# 1-Schematic_CarFan_controller_v2_0.net
KiCad netlist of a schematic drawn in EasyEDA
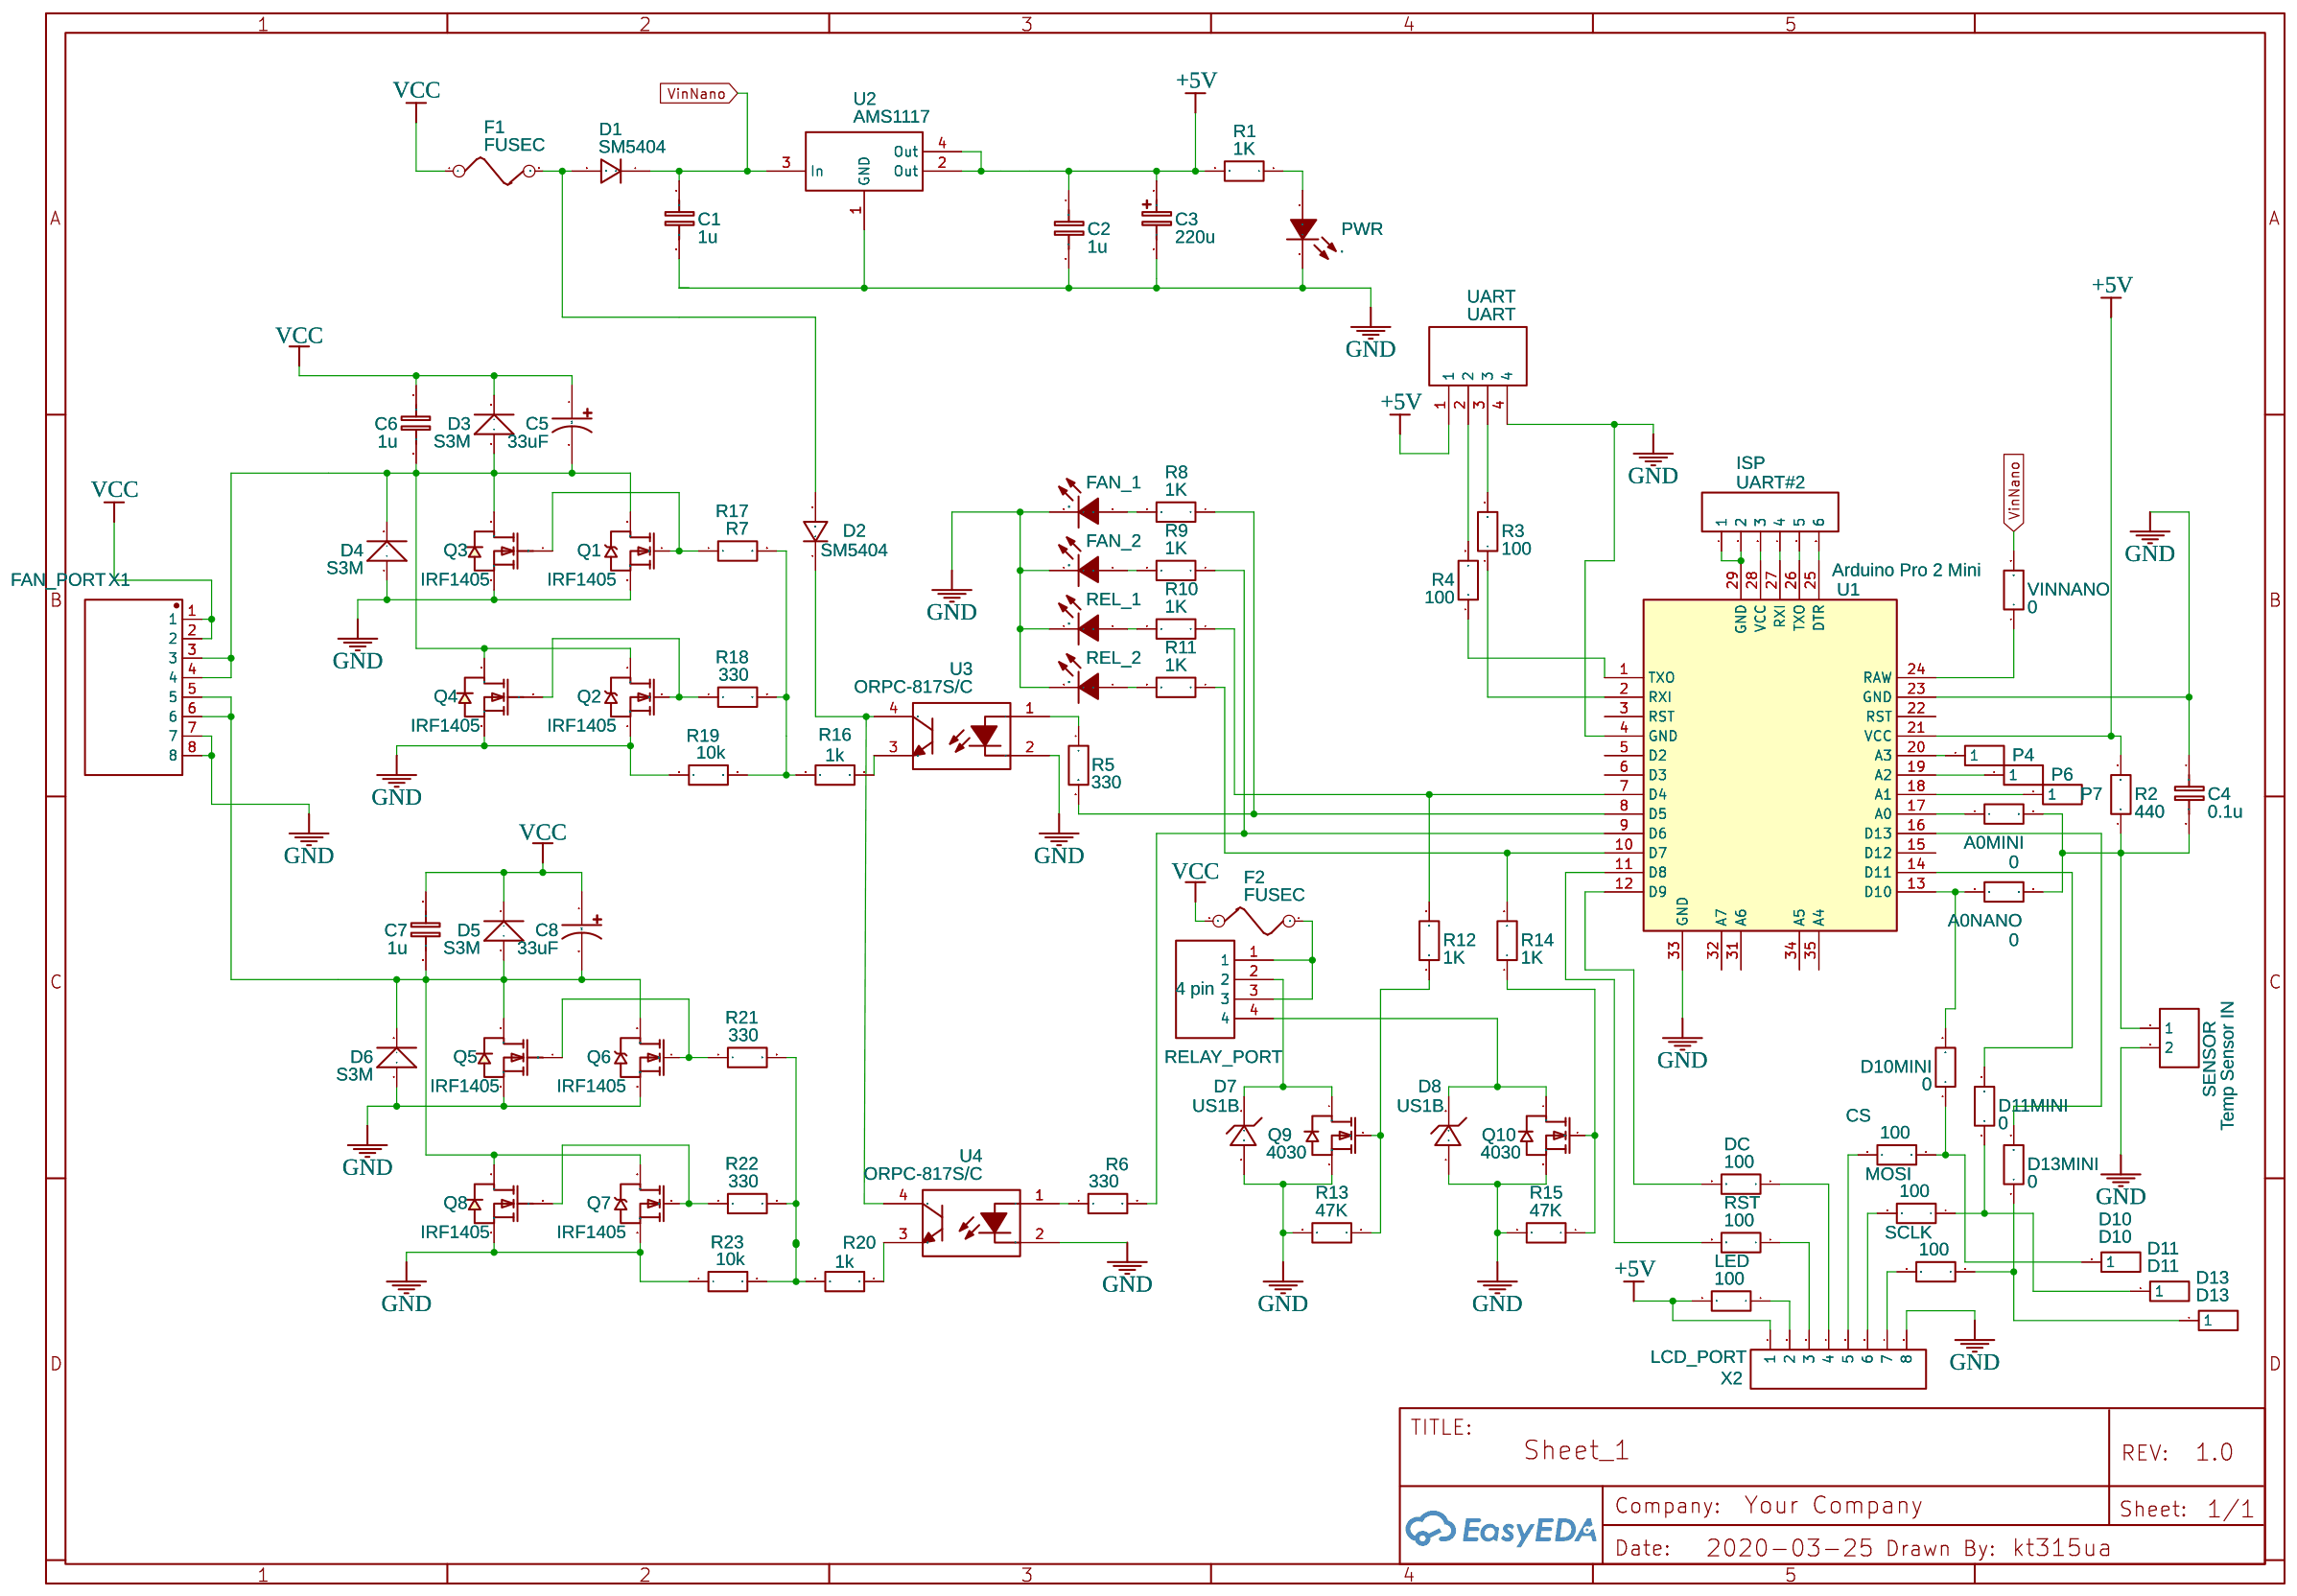
[diagram p0: schematic sheet]

(export (version "E")
  (design (tool "Eeschema 10.0.6"))
  (components
    (comp (ref "A0MINI") (value "0") (libsource (lib "") (part "Res_1206(1/4W)_EU_15")))
    (comp (ref "A0NANO") (value "0") (libsource (lib "") (part "Res_1206(1/4W)_EU_12")))
    (comp (ref "C1") (value "1u") (libsource (lib "") (part "Cap_1206_EU_4")))
    (comp (ref "C2") (value "1u") (libsource (lib "") (part "Cap_1206_EU_2")))
    (comp (ref "C3") (value "220u") (libsource (lib "") (part "Cap_Electrolytic(SMD)_D6.3XH5.5_EU")))
    (comp (ref "C4") (value "0.1u") (libsource (lib "") (part "Cap_1206_EU_3")))
    (comp (ref "C5")
      (value "33uF")
      (fields
        (field (name "BOM_Manufacturer Part") "EEEFK2A330P")
        (field (name "BOM_Supplier Part") "C178571")
      )
      (libsource (lib "") (part "EEEFK2A330P"))
    )
    (comp (ref "C6") (value "1u") (libsource (lib "") (part "Cap_1206_EU_1")))
    (comp (ref "C7") (value "1u") (libsource (lib "") (part "Cap_1206_EU")))
    (comp (ref "C8")
      (value "33uF")
      (fields
        (field (name "BOM_Manufacturer Part") "EEEFK2A330P")
        (field (name "BOM_Supplier Part") "C178571")
      )
      (libsource (lib "") (part "EEEFK2A330P"))
    )
    (comp (ref "CS") (value "100") (libsource (lib "") (part "Res_1206(1/4W)_EU_14")))
    (comp (ref "D1")
      (value "SM5404")
      (fields (field (name "BOM_Supplier Part") "C212808"))
      (libsource (lib "") (part "SM5404"))
    )
    (comp (ref "D2")
      (value "SM5404")
      (fields (field (name "BOM_Supplier Part") "C212808"))
      (libsource (lib "") (part "SM5404_1"))
    )
    (comp (ref "D3") (value "S3M") (libsource (lib "") (part "DDO-214AB")))
    (comp (ref "D4") (value "S3M") (libsource (lib "") (part "DDO-214AB")))
    (comp (ref "D5") (value "S3M") (libsource (lib "") (part "DDO-214AB")))
    (comp (ref "D6") (value "S3M") (libsource (lib "") (part "DDO-214AB")))
    (comp (ref "D7")
      (value "US1B")
      (fields
        (field (name "BOM_Manufacturer Part") "SMAZ12-13-F")
        (field (name "BOM_Supplier Part") "C110523")
      )
      (libsource (lib "") (part "SMAZ12-13-F(SMA(DO-214AC))"))
    )
    (comp (ref "D8")
      (value "US1B")
      (fields
        (field (name "BOM_Manufacturer Part") "SMAZ12-13-F")
        (field (name "BOM_Supplier Part") "C110523")
      )
      (libsource (lib "") (part "SMAZ12-13-F(SMA(DO-214AC))"))
    )
    (comp (ref "D10")
      (value "D10")
      (fields
        (field (name "BOM_Manufacturer Part") "Header-Male-2.54_1x1")
        (field (name "BOM_Supplier Part") "C81276")
      )
      (libsource (lib "") (part "Header-Male-2.54_1x1_1"))
    )
    (comp (ref "D10MINI") (value "0") (libsource (lib "") (part "Res_1206(1/4W)_EU_4")))
    (comp (ref "D11")
      (value "D11")
      (fields
        (field (name "BOM_Manufacturer Part") "Header-Male-2.54_1x1")
        (field (name "BOM_Supplier Part") "C81276")
      )
      (libsource (lib "") (part "Header-Male-2.54_1x1_1"))
    )
    (comp (ref "D11MINI") (value "0") (libsource (lib "") (part "Res_1206(1/4W)_EU_11")))
    (comp (ref "D13")
      (value "D13")
      (fields
        (field (name "BOM_Manufacturer Part") "Header-Male-2.54_1x1")
        (field (name "BOM_Supplier Part") "C81276")
      )
      (libsource (lib "") (part "Header-Male-2.54_1x1_1"))
    )
    (comp (ref "D13MINI") (value "0") (libsource (lib "") (part "Res_1206(1/4W)_EU_2")))
    (comp (ref "DC") (value "100") (libsource (lib "") (part "Res_1206(1/4W)_EU_9")))
    (comp (ref "F1") (value "FUSEC") (libsource (lib "") (part "FUSEC_1")))
    (comp (ref "F2") (value "FUSEC") (libsource (lib "") (part "FUSEC")))
    (comp (ref "FAN_1")
      (value ".")
      (fields
        (field (name "BOM_Manufacturer Part") "KT-1206Red LED")
        (field (name "BOM_Supplier Part") "C49018")
      )
      (libsource (lib "") (part "KT-1206Red LED"))
    )
    (comp (ref "FAN_2")
      (value ".")
      (fields
        (field (name "BOM_Manufacturer Part") "KT-1206Red LED")
        (field (name "BOM_Supplier Part") "C49018")
      )
      (libsource (lib "") (part "KT-1206Red LED"))
    )
    (comp (ref "FAN_PORT")
      (value "X1")
      (fields
        (field (name "BOM_Manufacturer Part") "Connector KF2510-8A")
        (field (name "BOM_Supplier Part") "C27837")
      )
      (libsource (lib "") (part "Connector_KF2510-8A-Fix"))
    )
    (comp (ref "ISP")
      (value "UART#2")
      (fields
        (field (name "BOM_Manufacturer Part") "Female header 1*6p")
        (field (name "BOM_Supplier Part") "C40877")
      )
      (libsource (lib "") (part "Header-Female-2.54_1x6"))
    )
    (comp (ref "LCD_PORT")
      (value "X2")
      (fields
        (field (name "BOM_Manufacturer Part") "Female headerHDR1X8-2.54")
        (field (name "BOM_Supplier Part") "C27438")
      )
      (libsource (lib "") (part "Header-Female-2.54_1x8"))
    )
    (comp (ref "LED") (value "100") (libsource (lib "") (part "Res_1206(1/4W)_EU_10")))
    (comp (ref "MOSI") (value "100") (libsource (lib "") (part "Res_1206(1/4W)_EU_3")))
    (comp (ref "P4")
      (value "D13")
      (fields
        (field (name "BOM_Manufacturer Part") "Header-Male-2.54_1x1")
        (field (name "BOM_Supplier Part") "C81276")
      )
      (libsource (lib "") (part "Header-Male-2.54_1x1"))
    )
    (comp (ref "P6")
      (value "D13")
      (fields
        (field (name "BOM_Manufacturer Part") "Header-Male-2.54_1x1")
        (field (name "BOM_Supplier Part") "C81276")
      )
      (libsource (lib "") (part "Header-Male-2.54_1x1"))
    )
    (comp (ref "P7")
      (value "D13")
      (fields
        (field (name "BOM_Manufacturer Part") "Header-Male-2.54_1x1")
        (field (name "BOM_Supplier Part") "C81276")
      )
      (libsource (lib "") (part "Header-Male-2.54_1x1"))
    )
    (comp (ref "PWR")
      (value ".")
      (fields
        (field (name "BOM_Manufacturer Part") "KT-1206Red LED")
        (field (name "BOM_Supplier Part") "C49018")
      )
      (libsource (lib "") (part "KT-1206Red LED_2"))
    )
    (comp (ref "Q1")
      (value "IRF1405")
      (fields
        (field (name "BOM_Manufacturer Part") "IRF1405ZSTRLPBF")
        (field (name "BOM_Supplier Part") "C459941")
      )
      (libsource (lib "") (part "IRF1405ZSTRLPBF"))
    )
    (comp (ref "Q2")
      (value "IRF1405")
      (fields
        (field (name "BOM_Manufacturer Part") "IRF1405ZSTRLPBF")
        (field (name "BOM_Supplier Part") "C459941")
      )
      (libsource (lib "") (part "IRF1405ZSTRLPBF"))
    )
    (comp (ref "Q3")
      (value "IRF1405")
      (fields (field (name "BOM_Manufacturer Part") "IRF1405PBF") (field (name "BOM_Supplier Part") "C2559"))
      (libsource (lib "") (part "IRF1405PBF"))
    )
    (comp (ref "Q4")
      (value "IRF1405")
      (fields (field (name "BOM_Manufacturer Part") "IRF1405PBF") (field (name "BOM_Supplier Part") "C2559"))
      (libsource (lib "") (part "IRF1405PBF"))
    )
    (comp (ref "Q5")
      (value "IRF1405")
      (fields (field (name "BOM_Manufacturer Part") "IRF1405PBF") (field (name "BOM_Supplier Part") "C2559"))
      (libsource (lib "") (part "IRF1405PBF"))
    )
    (comp (ref "Q6")
      (value "IRF1405")
      (fields
        (field (name "BOM_Manufacturer Part") "IRF1405ZSTRLPBF")
        (field (name "BOM_Supplier Part") "C459941")
      )
      (libsource (lib "") (part "IRF1405ZSTRLPBF"))
    )
    (comp (ref "Q7")
      (value "IRF1405")
      (fields
        (field (name "BOM_Manufacturer Part") "IRF1405ZSTRLPBF")
        (field (name "BOM_Supplier Part") "C459941")
      )
      (libsource (lib "") (part "IRF1405ZSTRLPBF"))
    )
    (comp (ref "Q8")
      (value "IRF1405")
      (fields (field (name "BOM_Manufacturer Part") "IRF1405PBF") (field (name "BOM_Supplier Part") "C2559"))
      (libsource (lib "") (part "IRF1405PBF"))
    )
    (comp (ref "Q9")
      (value "4030")
      (fields
        (field (name "BOM_Manufacturer Part") "STD8N60DM2")
        (field (name "BOM_Supplier Part") "C457504")
      )
      (libsource (lib "") (part "STD8N60DM2"))
    )
    (comp (ref "Q10")
      (value "4030")
      (fields
        (field (name "BOM_Manufacturer Part") "STD8N60DM2")
        (field (name "BOM_Supplier Part") "C457504")
      )
      (libsource (lib "") (part "STD8N60DM2"))
    )
    (comp (ref "R1") (value "1K") (libsource (lib "") (part "Res_1206(1/4W)_EU_1")))
    (comp (ref "R2") (value "440") (libsource (lib "") (part "Res_1206(1/4W)_EU_5")))
    (comp (ref "R3") (value "100") (libsource (lib "") (part "Res_1206(1/4W)_EU_5")))
    (comp (ref "R4") (value "100") (libsource (lib "") (part "Res_1206(1/4W)_EU_5")))
    (comp (ref "R5") (value "330") (libsource (lib "") (part "Res_1206(1/4W)_EU_6")))
    (comp (ref "R6") (value "330") (libsource (lib "") (part "Res_1206(1/4W)_EU")))
    (comp (ref "R8") (value "1K") (libsource (lib "") (part "Res_1206(1/4W)_EU_1")))
    (comp (ref "R9") (value "1K") (libsource (lib "") (part "Res_1206(1/4W)_EU_1")))
    (comp (ref "R10") (value "1K") (libsource (lib "") (part "Res_1206(1/4W)_EU_1")))
    (comp (ref "R11") (value "1K") (libsource (lib "") (part "Res_1206(1/4W)_EU_1")))
    (comp (ref "R12") (value "1K") (libsource (lib "") (part "Res_1206(1/4W)_EU_5")))
    (comp (ref "R13") (value "47K") (libsource (lib "") (part "Res_1206(1/4W)_EU_1")))
    (comp (ref "R14") (value "1K") (libsource (lib "") (part "Res_1206(1/4W)_EU_5")))
    (comp (ref "R15") (value "47K") (libsource (lib "") (part "Res_1206(1/4W)_EU_1")))
    (comp (ref "R16") (value "1k") (libsource (lib "") (part "Res_1206(1/4W)_EU_1")))
    (comp (ref "R17") (value "R7") (libsource (lib "") (part "Res_1206(1/4W)_EU")))
    (comp (ref "R18") (value "330") (libsource (lib "") (part "Res_1206(1/4W)_EU")))
    (comp (ref "R19") (value "10k") (libsource (lib "") (part "Res_1206(1/4W)_EU")))
    (comp (ref "R20") (value "1k") (libsource (lib "") (part "Res_1206(1/4W)_EU_1")))
    (comp (ref "R21") (value "330") (libsource (lib "") (part "Res_1206(1/4W)_EU")))
    (comp (ref "R22") (value "330") (libsource (lib "") (part "Res_1206(1/4W)_EU")))
    (comp (ref "R23") (value "10k") (libsource (lib "") (part "Res_1206(1/4W)_EU")))
    (comp (ref "RELAY_PORT")
      (value "4 pin")
      (fields
        (field (name "BOM_Manufacturer Part") "220S-1*4P H=8.5MM Ytype Gold-plated")
        (field (name "BOM_Supplier Part") "C124413")
      )
      (libsource (lib "") (part "220S-1*4P H=8.5MM Ytype Gold-plated"))
    )
    (comp (ref "REL_1")
      (value ".")
      (fields
        (field (name "BOM_Manufacturer Part") "KT-1206Red LED")
        (field (name "BOM_Supplier Part") "C49018")
      )
      (libsource (lib "") (part "KT-1206Red LED_1"))
    )
    (comp (ref "REL_2")
      (value ".")
      (fields
        (field (name "BOM_Manufacturer Part") "KT-1206Red LED")
        (field (name "BOM_Supplier Part") "C49018")
      )
      (libsource (lib "") (part "KT-1206Red LED_1"))
    )
    (comp (ref "RST") (value "100") (libsource (lib "") (part "Res_1206(1/4W)_EU_7")))
    (comp (ref "SCLK") (value "100") (libsource (lib "") (part "Res_1206(1/4W)_EU_8")))
    (comp (ref "SENSOR")
      (value "Temp Sensor IN")
      (fields
        (field (name "BOM_Manufacturer Part") "2.54-1*2PFemale")
        (field (name "BOM_Supplier Part") "C49661")
      )
      (libsource (lib "") (part "Header-Female-2.54_1x2"))
    )
    (comp (ref "U1") (value "Arduino Pro 2 Mini") (libsource (lib "") (part "Arduino Pro 2 Mini_328_-_3.3V")))
    (comp (ref "U2")
      (value "AMS1117")
      (fields (field (name "BOM_Supplier Part") "C6186"))
      (libsource (lib "") (part "AMS1117"))
    )
    (comp (ref "U3")
      (value "ORPC-817S/C")
      (fields (field (name "BOM_Supplier Part") "C231230"))
      (libsource (lib "") (part "ORPC-817S/C"))
    )
    (comp (ref "U4")
      (value "ORPC-817S/C")
      (fields (field (name "BOM_Supplier Part") "C231230"))
      (libsource (lib "") (part "ORPC-817S/C"))
    )
    (comp (ref "UART")
      (value "UART")
      (fields
        (field (name "BOM_Manufacturer Part") "220S-1*4P H=8.5MM Ytype Gold-plated")
        (field (name "BOM_Supplier Part") "C124413")
      )
      (libsource (lib "") (part "220S-1*4P H=8.5MM Ytype Gold-plated_1"))
    )
    (comp (ref "VINNANO") (value "0") (libsource (lib "") (part "Res_1206(1/4W)_EU_13")))
  )
  (nets
    (net (code "1") (name "+5V") (class "Default")
      (node (ref "C2") (pin "1") (pinfunction "1_1") (pintype "unspecified"))
      (node (ref "C3") (pin "1") (pinfunction "1_1") (pintype "unspecified"))
      (node (ref "LCD_PORT") (pin "1") (pinfunction "1_1") (pintype "input"))
      (node (ref "LED") (pin "2") (pinfunction "2_2") (pintype "unspecified"))
      (node (ref "R1") (pin "2") (pinfunction "2_2") (pintype "unspecified"))
      (node (ref "R2") (pin "2") (pinfunction "2_2") (pintype "unspecified"))
      (node (ref "U1") (pin "21") (pinfunction "VCC_21") (pintype "unspecified"))
      (node (ref "U2") (pin "2") (pinfunction "Out_2") (pintype "unspecified"))
      (node (ref "U2") (pin "4") (pinfunction "Out_4") (pintype "unspecified"))
      (node (ref "UART") (pin "1") (pinfunction "1_1") (pintype "unspecified"))
    )
    (net (code "2") (name "GND") (class "Default")
      (node (ref "C1") (pin "2") (pinfunction "2_2") (pintype "unspecified"))
      (node (ref "C2") (pin "2") (pinfunction "2_2") (pintype "unspecified"))
      (node (ref "C3") (pin "2") (pinfunction "2_2") (pintype "unspecified"))
      (node (ref "C4") (pin "1") (pinfunction "1_1") (pintype "unspecified"))
      (node (ref "D4") (pin "1") (pinfunction "+_1") (pintype "unspecified"))
      (node (ref "D6") (pin "1") (pinfunction "+_1") (pintype "unspecified"))
      (node (ref "D7") (pin "1") (pinfunction "A_1") (pintype "unspecified"))
      (node (ref "D8") (pin "1") (pinfunction "A_1") (pintype "unspecified"))
      (node (ref "FAN_1") (pin "2") (pinfunction "K_2") (pintype "unspecified"))
      (node (ref "FAN_2") (pin "2") (pinfunction "K_2") (pintype "unspecified"))
      (node (ref "FAN_PORT") (pin "7") (pinfunction "7_7") (pintype "unspecified"))
      (node (ref "FAN_PORT") (pin "8") (pinfunction "8_8") (pintype "unspecified"))
      (node (ref "LCD_PORT") (pin "8") (pinfunction "8_8") (pintype "input"))
      (node (ref "PWR") (pin "2") (pinfunction "K_2") (pintype "unspecified"))
      (node (ref "Q1") (pin "3") (pinfunction "S_3") (pintype "unspecified"))
      (node (ref "Q10") (pin "3") (pinfunction "S_3") (pintype "unspecified"))
      (node (ref "Q2") (pin "3") (pinfunction "S_3") (pintype "unspecified"))
      (node (ref "Q3") (pin "3") (pinfunction "S_3") (pintype "unspecified"))
      (node (ref "Q4") (pin "3") (pinfunction "S_3") (pintype "unspecified"))
      (node (ref "Q5") (pin "3") (pinfunction "S_3") (pintype "unspecified"))
      (node (ref "Q6") (pin "3") (pinfunction "S_3") (pintype "unspecified"))
      (node (ref "Q7") (pin "3") (pinfunction "S_3") (pintype "unspecified"))
      (node (ref "Q8") (pin "3") (pinfunction "S_3") (pintype "unspecified"))
      (node (ref "Q9") (pin "3") (pinfunction "S_3") (pintype "unspecified"))
      (node (ref "R13") (pin "2") (pinfunction "2_2") (pintype "unspecified"))
      (node (ref "R15") (pin "2") (pinfunction "2_2") (pintype "unspecified"))
      (node (ref "R19") (pin "1") (pinfunction "1_1") (pintype "unspecified"))
      (node (ref "R23") (pin "1") (pinfunction "1_1") (pintype "unspecified"))
      (node (ref "REL_1") (pin "2") (pinfunction "K_2") (pintype "unspecified"))
      (node (ref "REL_2") (pin "2") (pinfunction "K_2") (pintype "unspecified"))
      (node (ref "SENSOR") (pin "2") (pinfunction "2_2") (pintype "input"))
      (node (ref "U1") (pin "23") (pinfunction "GND_23") (pintype "unspecified"))
      (node (ref "U1") (pin "33") (pinfunction "GND_33") (pintype "unspecified"))
      (node (ref "U1") (pin "4") (pinfunction "GND_4") (pintype "unspecified"))
      (node (ref "U2") (pin "1") (pinfunction "GND_1") (pintype "unspecified"))
      (node (ref "U3") (pin "2") (pinfunction "2_2") (pintype "unspecified"))
      (node (ref "U4") (pin "2") (pinfunction "2_2") (pintype "unspecified"))
      (node (ref "UART") (pin "4") (pinfunction "4_4") (pintype "unspecified"))
    )
    (net (code "3") (name "Net-(A0MINI-Pad2)") (class "Default")
      (node (ref "A0MINI") (pin "2") (pinfunction "2_2") (pintype "unspecified"))
      (node (ref "A0NANO") (pin "2") (pinfunction "2_2") (pintype "unspecified"))
      (node (ref "C4") (pin "2") (pinfunction "2_2") (pintype "unspecified"))
      (node (ref "R2") (pin "1") (pinfunction "1_1") (pintype "unspecified"))
      (node (ref "SENSOR") (pin "1") (pinfunction "1_1") (pintype "input"))
    )
    (net (code "4") (name "Net-(CS-Pad1)") (class "Default")
      (node (ref "CS") (pin "1") (pinfunction "1_1") (pintype "unspecified"))
      (node (ref "D10") (pin "1") (pinfunction "1_1") (pintype "input"))
      (node (ref "D10MINI") (pin "1") (pinfunction "1_1") (pintype "unspecified"))
    )
    (net (code "5") (name "Net-(CS-Pad2)") (class "Default")
      (node (ref "CS") (pin "2") (pinfunction "2_2") (pintype "unspecified"))
      (node (ref "LCD_PORT") (pin "5") (pinfunction "5_5") (pintype "input"))
    )
    (net (code "6") (name "Net-(D1-Pad2)") (class "Default")
      (node (ref "D1") (pin "2") (pinfunction "2_2") (pintype "unspecified"))
      (node (ref "D2") (pin "2") (pinfunction "2_2") (pintype "unspecified"))
      (node (ref "F1") (pin "2") (pinfunction "2_2") (pintype "unspecified"))
    )
    (net (code "7") (name "Net-(D2-Pad1)") (class "Default")
      (node (ref "D2") (pin "1") (pinfunction "1_1") (pintype "unspecified"))
      (node (ref "U3") (pin "4") (pinfunction "4_4") (pintype "unspecified"))
      (node (ref "U4") (pin "4") (pinfunction "4_4") (pintype "unspecified"))
    )
    (net (code "8") (name "Net-(D3-+)") (class "Default")
      (node (ref "C5") (pin "2") (pinfunction "2_2") (pintype "unspecified"))
      (node (ref "C6") (pin "2") (pinfunction "2_2") (pintype "unspecified"))
      (node (ref "D3") (pin "1") (pinfunction "+_1") (pintype "unspecified"))
      (node (ref "D4") (pin "2") (pinfunction "-_2") (pintype "unspecified"))
      (node (ref "FAN_PORT") (pin "3") (pinfunction "3_3") (pintype "unspecified"))
      (node (ref "FAN_PORT") (pin "4") (pinfunction "4_4") (pintype "unspecified"))
      (node (ref "Q1") (pin "2") (pinfunction "D_2") (pintype "unspecified"))
      (node (ref "Q2") (pin "2") (pinfunction "D_2") (pintype "unspecified"))
      (node (ref "Q3") (pin "2") (pinfunction "D_2") (pintype "unspecified"))
      (node (ref "Q4") (pin "2") (pinfunction "D_2") (pintype "unspecified"))
    )
    (net (code "9") (name "Net-(D5-+)") (class "Default")
      (node (ref "C7") (pin "2") (pinfunction "2_2") (pintype "unspecified"))
      (node (ref "C8") (pin "2") (pinfunction "2_2") (pintype "unspecified"))
      (node (ref "D5") (pin "1") (pinfunction "+_1") (pintype "unspecified"))
      (node (ref "D6") (pin "2") (pinfunction "-_2") (pintype "unspecified"))
      (node (ref "FAN_PORT") (pin "5") (pinfunction "5_5") (pintype "unspecified"))
      (node (ref "FAN_PORT") (pin "6") (pinfunction "6_6") (pintype "unspecified"))
      (node (ref "Q5") (pin "2") (pinfunction "D_2") (pintype "unspecified"))
      (node (ref "Q6") (pin "2") (pinfunction "D_2") (pintype "unspecified"))
      (node (ref "Q7") (pin "2") (pinfunction "D_2") (pintype "unspecified"))
      (node (ref "Q8") (pin "2") (pinfunction "D_2") (pintype "unspecified"))
    )
    (net (code "10") (name "Net-(D7-K)") (class "Default")
      (node (ref "D7") (pin "2") (pinfunction "K_2") (pintype "unspecified"))
      (node (ref "Q9") (pin "4") (pinfunction "D_4") (pintype "unspecified"))
      (node (ref "RELAY_PORT") (pin "2") (pinfunction "2_2") (pintype "unspecified"))
    )
    (net (code "11") (name "Net-(D8-K)") (class "Default")
      (node (ref "D8") (pin "2") (pinfunction "K_2") (pintype "unspecified"))
      (node (ref "Q10") (pin "4") (pinfunction "D_4") (pintype "unspecified"))
      (node (ref "RELAY_PORT") (pin "4") (pinfunction "4_4") (pintype "unspecified"))
    )
    (net (code "12") (name "Net-(D11-Pad1)") (class "Default")
      (node (ref "D11") (pin "1") (pinfunction "1_1") (pintype "input"))
      (node (ref "D11MINI") (pin "1") (pinfunction "1_1") (pintype "unspecified"))
      (node (ref "MOSI") (pin "1") (pinfunction "1_1") (pintype "unspecified"))
    )
    (net (code "13") (name "Net-(D13-Pad1)") (class "Default")
      (node (ref "D13") (pin "1") (pinfunction "1_1") (pintype "input"))
      (node (ref "D13MINI") (pin "1") (pinfunction "1_1") (pintype "unspecified"))
      (node (ref "SCLK") (pin "1") (pinfunction "1_1") (pintype "unspecified"))
    )
    (net (code "14") (name "Net-(DC-Pad1)") (class "Default")
      (node (ref "DC") (pin "1") (pinfunction "1_1") (pintype "unspecified"))
      (node (ref "LCD_PORT") (pin "4") (pinfunction "4_4") (pintype "input"))
    )
    (net (code "15") (name "Net-(F2-Pad1)") (class "Default")
      (node (ref "F2") (pin "1") (pinfunction "1_1") (pintype "unspecified"))
      (node (ref "RELAY_PORT") (pin "1") (pinfunction "1_1") (pintype "unspecified"))
      (node (ref "RELAY_PORT") (pin "3") (pinfunction "3_3") (pintype "unspecified"))
    )
    (net (code "16") (name "Net-(FAN_1-A)") (class "Default")
      (node (ref "FAN_1") (pin "1") (pinfunction "A_1") (pintype "unspecified"))
      (node (ref "R8") (pin "2") (pinfunction "2_2") (pintype "unspecified"))
    )
    (net (code "17") (name "Net-(FAN_2-A)") (class "Default")
      (node (ref "FAN_2") (pin "1") (pinfunction "A_1") (pintype "unspecified"))
      (node (ref "R9") (pin "2") (pinfunction "2_2") (pintype "unspecified"))
    )
    (net (code "18") (name "Net-(ISP-Pad1)") (class "Default")
      (node (ref "ISP") (pin "1") (pinfunction "1_1") (pintype "input"))
      (node (ref "ISP") (pin "2") (pinfunction "2_2") (pintype "input"))
      (node (ref "U1") (pin "29") (pinfunction "GND_29") (pintype "unspecified"))
    )
    (net (code "19") (name "Net-(ISP-Pad3)") (class "Default")
      (node (ref "ISP") (pin "3") (pinfunction "3_3") (pintype "input"))
      (node (ref "U1") (pin "28") (pinfunction "VCC_28") (pintype "unspecified"))
    )
    (net (code "20") (name "Net-(ISP-Pad4)") (class "Default")
      (node (ref "ISP") (pin "4") (pinfunction "4_4") (pintype "input"))
      (node (ref "U1") (pin "27") (pinfunction "RXI_27") (pintype "unspecified"))
    )
    (net (code "21") (name "Net-(ISP-Pad5)") (class "Default")
      (node (ref "ISP") (pin "5") (pinfunction "5_5") (pintype "input"))
      (node (ref "U1") (pin "26") (pinfunction "TXO_26") (pintype "unspecified"))
    )
    (net (code "22") (name "Net-(LCD_PORT-Pad2)") (class "Default")
      (node (ref "LCD_PORT") (pin "2") (pinfunction "2_2") (pintype "input"))
      (node (ref "LED") (pin "1") (pinfunction "1_1") (pintype "unspecified"))
    )
    (net (code "23") (name "Net-(LCD_PORT-Pad3)") (class "Default")
      (node (ref "LCD_PORT") (pin "3") (pinfunction "3_3") (pintype "input"))
      (node (ref "RST") (pin "1") (pinfunction "1_1") (pintype "unspecified"))
    )
    (net (code "24") (name "Net-(LCD_PORT-Pad6)") (class "Default")
      (node (ref "LCD_PORT") (pin "6") (pinfunction "6_6") (pintype "input"))
      (node (ref "MOSI") (pin "2") (pinfunction "2_2") (pintype "unspecified"))
    )
    (net (code "25") (name "Net-(LCD_PORT-Pad7)") (class "Default")
      (node (ref "LCD_PORT") (pin "7") (pinfunction "7_7") (pintype "input"))
      (node (ref "SCLK") (pin "2") (pinfunction "2_2") (pintype "unspecified"))
    )
    (net (code "26") (name "Net-(PWR-A)") (class "Default")
      (node (ref "PWR") (pin "1") (pinfunction "A_1") (pintype "unspecified"))
      (node (ref "R1") (pin "1") (pinfunction "1_1") (pintype "unspecified"))
    )
    (net (code "27") (name "Net-(Q1-G)") (class "Default")
      (node (ref "Q1") (pin "1") (pinfunction "G_1") (pintype "unspecified"))
      (node (ref "Q3") (pin "1") (pinfunction "G_1") (pintype "unspecified"))
      (node (ref "R17") (pin "1") (pinfunction "1_1") (pintype "unspecified"))
    )
    (net (code "28") (name "Net-(Q2-G)") (class "Default")
      (node (ref "Q2") (pin "1") (pinfunction "G_1") (pintype "unspecified"))
      (node (ref "Q4") (pin "1") (pinfunction "G_1") (pintype "unspecified"))
      (node (ref "R18") (pin "1") (pinfunction "1_1") (pintype "unspecified"))
    )
    (net (code "29") (name "Net-(Q5-G)") (class "Default")
      (node (ref "Q5") (pin "1") (pinfunction "G_1") (pintype "unspecified"))
      (node (ref "Q6") (pin "1") (pinfunction "G_1") (pintype "unspecified"))
      (node (ref "R21") (pin "1") (pinfunction "1_1") (pintype "unspecified"))
    )
    (net (code "30") (name "Net-(Q7-G)") (class "Default")
      (node (ref "Q7") (pin "1") (pinfunction "G_1") (pintype "unspecified"))
      (node (ref "Q8") (pin "1") (pinfunction "G_1") (pintype "unspecified"))
      (node (ref "R22") (pin "1") (pinfunction "1_1") (pintype "unspecified"))
    )
    (net (code "31") (name "Net-(Q9-G)") (class "Default")
      (node (ref "Q9") (pin "1") (pinfunction "G_1") (pintype "unspecified"))
      (node (ref "R12") (pin "1") (pinfunction "1_1") (pintype "unspecified"))
      (node (ref "R13") (pin "1") (pinfunction "1_1") (pintype "unspecified"))
    )
    (net (code "32") (name "Net-(Q10-G)") (class "Default")
      (node (ref "Q10") (pin "1") (pinfunction "G_1") (pintype "unspecified"))
      (node (ref "R14") (pin "1") (pinfunction "1_1") (pintype "unspecified"))
      (node (ref "R15") (pin "1") (pinfunction "1_1") (pintype "unspecified"))
    )
    (net (code "33") (name "Net-(R3-Pad1)") (class "Default")
      (node (ref "R3") (pin "1") (pinfunction "1_1") (pintype "unspecified"))
      (node (ref "U1") (pin "2") (pinfunction "RXI_2") (pintype "unspecified"))
    )
    (net (code "34") (name "Net-(R3-Pad2)") (class "Default")
      (node (ref "R3") (pin "2") (pinfunction "2_2") (pintype "unspecified"))
      (node (ref "UART") (pin "3") (pinfunction "3_3") (pintype "unspecified"))
    )
    (net (code "35") (name "Net-(R4-Pad1)") (class "Default")
      (node (ref "R4") (pin "1") (pinfunction "1_1") (pintype "unspecified"))
      (node (ref "U1") (pin "1") (pinfunction "TXO_1") (pintype "unspecified"))
    )
    (net (code "36") (name "Net-(R4-Pad2)") (class "Default")
      (node (ref "R4") (pin "2") (pinfunction "2_2") (pintype "unspecified"))
      (node (ref "UART") (pin "2") (pinfunction "2_2") (pintype "unspecified"))
    )
    (net (code "37") (name "Net-(R5-Pad1)") (class "Default")
      (node (ref "R5") (pin "1") (pinfunction "1_1") (pintype "unspecified"))
      (node (ref "U3") (pin "1") (pinfunction "1_1") (pintype "unspecified"))
    )
    (net (code "38") (name "Net-(R6-Pad1)") (class "Default")
      (node (ref "R6") (pin "1") (pinfunction "1_1") (pintype "unspecified"))
      (node (ref "U4") (pin "1") (pinfunction "1_1") (pintype "unspecified"))
    )
    (net (code "39") (name "Net-(R16-Pad1)") (class "Default")
      (node (ref "R16") (pin "1") (pinfunction "1_1") (pintype "unspecified"))
      (node (ref "U3") (pin "3") (pinfunction "3_3") (pintype "unspecified"))
    )
    (net (code "40") (name "Net-(R16-Pad2)") (class "Default")
      (node (ref "R16") (pin "2") (pinfunction "2_2") (pintype "unspecified"))
      (node (ref "R17") (pin "2") (pinfunction "2_2") (pintype "unspecified"))
      (node (ref "R18") (pin "2") (pinfunction "2_2") (pintype "unspecified"))
      (node (ref "R19") (pin "2") (pinfunction "2_2") (pintype "unspecified"))
    )
    (net (code "41") (name "Net-(R20-Pad1)") (class "Default")
      (node (ref "R20") (pin "1") (pinfunction "1_1") (pintype "unspecified"))
      (node (ref "U4") (pin "3") (pinfunction "3_3") (pintype "unspecified"))
    )
    (net (code "42") (name "Net-(R20-Pad2)") (class "Default")
      (node (ref "R20") (pin "2") (pinfunction "2_2") (pintype "unspecified"))
      (node (ref "R21") (pin "2") (pinfunction "2_2") (pintype "unspecified"))
      (node (ref "R22") (pin "2") (pinfunction "2_2") (pintype "unspecified"))
      (node (ref "R23") (pin "2") (pinfunction "2_2") (pintype "unspecified"))
    )
    (net (code "43") (name "Net-(REL_1-A)") (class "Default")
      (node (ref "R10") (pin "2") (pinfunction "2_2") (pintype "unspecified"))
      (node (ref "REL_1") (pin "1") (pinfunction "A_1") (pintype "unspecified"))
    )
    (net (code "44") (name "Net-(REL_2-A)") (class "Default")
      (node (ref "R11") (pin "2") (pinfunction "2_2") (pintype "unspecified"))
      (node (ref "REL_2") (pin "1") (pinfunction "A_1") (pintype "unspecified"))
    )
    (net (code "45") (name "Net-(U1-A0)") (class "Default")
      (node (ref "A0MINI") (pin "1") (pinfunction "1_1") (pintype "unspecified"))
      (node (ref "U1") (pin "17") (pinfunction "A0_17") (pintype "unspecified"))
    )
    (net (code "46") (name "Net-(U1-A1)") (class "Default")
      (node (ref "P7") (pin "1") (pinfunction "1_1") (pintype "input"))
      (node (ref "U1") (pin "18") (pinfunction "A1_18") (pintype "unspecified"))
    )
    (net (code "47") (name "Net-(U1-A2)") (class "Default")
      (node (ref "P6") (pin "1") (pinfunction "1_1") (pintype "input"))
      (node (ref "U1") (pin "19") (pinfunction "A2_19") (pintype "unspecified"))
    )
    (net (code "48") (name "Net-(U1-A3)") (class "Default")
      (node (ref "P4") (pin "1") (pinfunction "1_1") (pintype "input"))
      (node (ref "U1") (pin "20") (pinfunction "A3_20") (pintype "unspecified"))
    )
    (net (code "49") (name "Net-(U1-D4)") (class "Default")
      (node (ref "R10") (pin "1") (pinfunction "1_1") (pintype "unspecified"))
      (node (ref "R12") (pin "2") (pinfunction "2_2") (pintype "unspecified"))
      (node (ref "U1") (pin "7") (pinfunction "D4_7") (pintype "unspecified"))
    )
    (net (code "50") (name "Net-(U1-D5)") (class "Default")
      (node (ref "R5") (pin "2") (pinfunction "2_2") (pintype "unspecified"))
      (node (ref "R8") (pin "1") (pinfunction "1_1") (pintype "unspecified"))
      (node (ref "U1") (pin "8") (pinfunction "D5_8") (pintype "unspecified"))
    )
    (net (code "51") (name "Net-(U1-D6)") (class "Default")
      (node (ref "R6") (pin "2") (pinfunction "2_2") (pintype "unspecified"))
      (node (ref "R9") (pin "1") (pinfunction "1_1") (pintype "unspecified"))
      (node (ref "U1") (pin "9") (pinfunction "D6_9") (pintype "unspecified"))
    )
    (net (code "52") (name "Net-(U1-D7)") (class "Default")
      (node (ref "R11") (pin "1") (pinfunction "1_1") (pintype "unspecified"))
      (node (ref "R14") (pin "2") (pinfunction "2_2") (pintype "unspecified"))
      (node (ref "U1") (pin "10") (pinfunction "D7_10") (pintype "unspecified"))
    )
    (net (code "53") (name "Net-(U1-D8)") (class "Default")
      (node (ref "RST") (pin "2") (pinfunction "2_2") (pintype "unspecified"))
      (node (ref "U1") (pin "11") (pinfunction "D8_11") (pintype "unspecified"))
    )
    (net (code "54") (name "Net-(U1-D9)") (class "Default")
      (node (ref "DC") (pin "2") (pinfunction "2_2") (pintype "unspecified"))
      (node (ref "U1") (pin "12") (pinfunction "D9_12") (pintype "unspecified"))
    )
    (net (code "55") (name "Net-(U1-D10)") (class "Default")
      (node (ref "A0NANO") (pin "1") (pinfunction "1_1") (pintype "unspecified"))
      (node (ref "D10MINI") (pin "2") (pinfunction "2_2") (pintype "unspecified"))
      (node (ref "U1") (pin "13") (pinfunction "D10_13") (pintype "unspecified"))
    )
    (net (code "56") (name "Net-(U1-D11)") (class "Default")
      (node (ref "D11MINI") (pin "2") (pinfunction "2_2") (pintype "unspecified"))
      (node (ref "U1") (pin "14") (pinfunction "D11_14") (pintype "unspecified"))
    )
    (net (code "57") (name "Net-(U1-D13)") (class "Default")
      (node (ref "D13MINI") (pin "2") (pinfunction "2_2") (pintype "unspecified"))
      (node (ref "U1") (pin "16") (pinfunction "D13_16") (pintype "unspecified"))
    )
    (net (code "58") (name "Net-(U1-DTR)") (class "Default")
      (node (ref "ISP") (pin "6") (pinfunction "6_6") (pintype "input"))
      (node (ref "U1") (pin "25") (pinfunction "DTR_25") (pintype "unspecified"))
    )
    (net (code "59") (name "Net-(U1-RAW)") (class "Default")
      (node (ref "U1") (pin "24") (pinfunction "RAW_24") (pintype "unspecified"))
      (node (ref "VINNANO") (pin "1") (pinfunction "1_1") (pintype "unspecified"))
    )
    (net (code "60") (name "VCC") (class "Default")
      (node (ref "C5") (pin "1") (pinfunction "1_1") (pintype "unspecified"))
      (node (ref "C6") (pin "1") (pinfunction "1_1") (pintype "unspecified"))
      (node (ref "C7") (pin "1") (pinfunction "1_1") (pintype "unspecified"))
      (node (ref "C8") (pin "1") (pinfunction "1_1") (pintype "unspecified"))
      (node (ref "D3") (pin "2") (pinfunction "-_2") (pintype "unspecified"))
      (node (ref "D5") (pin "2") (pinfunction "-_2") (pintype "unspecified"))
      (node (ref "F1") (pin "1") (pinfunction "1_1") (pintype "unspecified"))
      (node (ref "F2") (pin "2") (pinfunction "2_2") (pintype "unspecified"))
      (node (ref "FAN_PORT") (pin "1") (pinfunction "1_1") (pintype "unspecified"))
      (node (ref "FAN_PORT") (pin "2") (pinfunction "2_2") (pintype "unspecified"))
    )
    (net (code "61") (name "VinNano") (class "Default")
      (node (ref "C1") (pin "1") (pinfunction "1_1") (pintype "unspecified"))
      (node (ref "D1") (pin "1") (pinfunction "1_1") (pintype "unspecified"))
      (node (ref "U2") (pin "3") (pinfunction "In_3") (pintype "unspecified"))
      (node (ref "VINNANO") (pin "2") (pinfunction "2_2") (pintype "unspecified"))
    )
    (net (code "62") (name "unconnected-(U1-A4-Pad35)") (class "Default")
      (node (ref "U1") (pin "35") (pinfunction "A4_35") (pintype "unspecified"))
    )
    (net (code "63") (name "unconnected-(U1-A5-Pad34)") (class "Default")
      (node (ref "U1") (pin "34") (pinfunction "A5_34") (pintype "unspecified"))
    )
    (net (code "64") (name "unconnected-(U1-A6-Pad31)") (class "Default")
      (node (ref "U1") (pin "31") (pinfunction "A6_31") (pintype "unspecified"))
    )
    (net (code "65") (name "unconnected-(U1-A7-Pad32)") (class "Default")
      (node (ref "U1") (pin "32") (pinfunction "A7_32") (pintype "unspecified"))
    )
    (net (code "66") (name "unconnected-(U1-D2-Pad5)") (class "Default")
      (node (ref "U1") (pin "5") (pinfunction "D2_5") (pintype "unspecified"))
    )
    (net (code "67") (name "unconnected-(U1-D3-Pad6)") (class "Default")
      (node (ref "U1") (pin "6") (pinfunction "D3_6") (pintype "unspecified"))
    )
    (net (code "68") (name "unconnected-(U1-D12-Pad15)") (class "Default")
      (node (ref "U1") (pin "15") (pinfunction "D12_15") (pintype "unspecified"))
    )
    (net (code "69") (name "unconnected-(U1-RST-Pad3)") (class "Default")
      (node (ref "U1") (pin "3") (pinfunction "RST_3") (pintype "unspecified"))
    )
    (net (code "70") (name "unconnected-(U1-RST-Pad22)") (class "Default")
      (node (ref "U1") (pin "22") (pinfunction "RST_22") (pintype "unspecified"))
    )
  )
)
